# mpc56_clk.net
KiCad netlist of a schematic drawn in Altium Designer
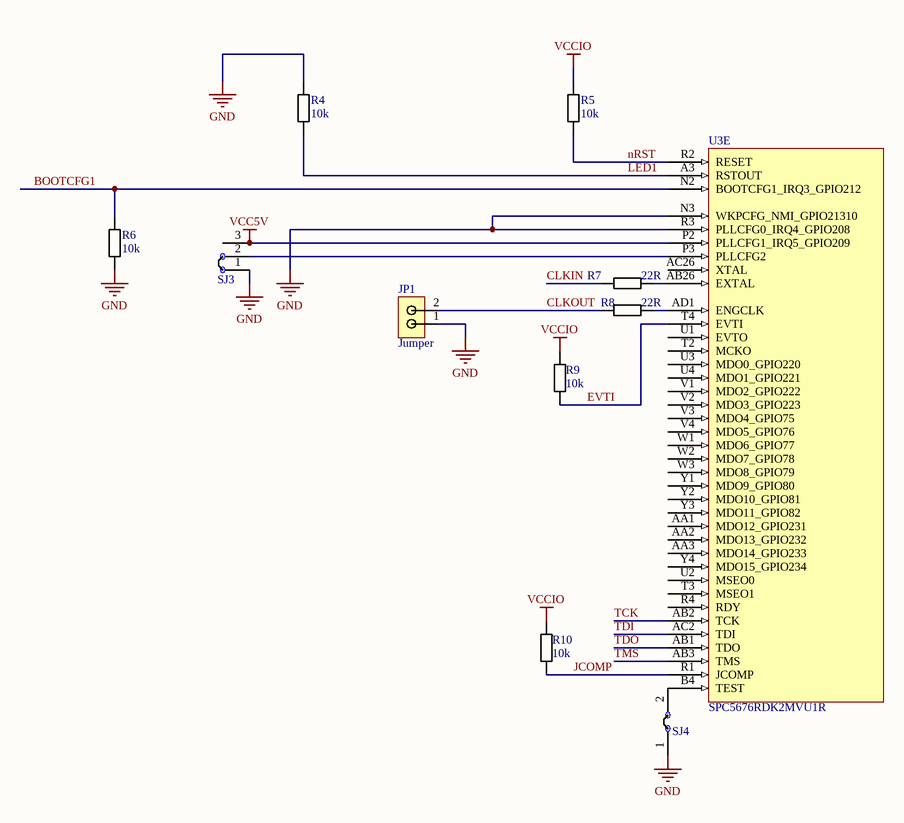
[diagram p0: mpc56_clk.SchDoc]

(export (version "E")
  (design (tool "Eeschema 10.0.6"))
  (components
    (comp (ref "JP1")
      (value "Jumper")
      (footprint "2x2.54mm_Header")
      (description "1x2 2.54mm header, male pins")
      (fields (field (name "PART NUMBER") "2_PIN_JUMPER"))
      (libsource (lib "NewAE_AltiumLib") (part "1x2_Pin_Header"))
    )
    (comp (ref "R4")
      (value "10k")
      (footprint "RESC1608X55N")
      (description "10k res, 0603, 1%, 1/10W")
      (fields (field (name "PART NUMBER") "RCHIP-10K-0603") (field (name "TOLERANCE") "1%"))
      (libsource (lib "NewAE_AltiumLib") (part "RES-EU"))
    )
    (comp (ref "R5")
      (value "10k")
      (footprint "RESC1608X55N")
      (description "10k res, 0603, 1%, 1/10W")
      (fields (field (name "PART NUMBER") "RCHIP-10K-0603") (field (name "TOLERANCE") "1%"))
      (libsource (lib "NewAE_AltiumLib") (part "RES-EU"))
    )
    (comp (ref "R6")
      (value "10k")
      (footprint "RESC1608X55N")
      (description "10k res, 0603, 1%, 1/10W")
      (fields (field (name "PART NUMBER") "RCHIP-10K-0603") (field (name "TOLERANCE") "1%"))
      (libsource (lib "NewAE_AltiumLib") (part "RES-EU"))
    )
    (comp (ref "R7")
      (value "22R")
      (footprint "RESC1608X55N")
      (description "22R res, 0603, 1%, 1/10W")
      (fields (field (name "PART NUMBER") "RCHIP-22R-0603") (field (name "TOLERANCE") "1%"))
      (libsource (lib "") (part "RES-EU_1"))
    )
    (comp (ref "R8")
      (value "22R")
      (footprint "RESC1608X55N")
      (description "22R res, 0603, 1%, 1/10W")
      (fields (field (name "PART NUMBER") "RCHIP-22R-0603") (field (name "TOLERANCE") "1%"))
      (libsource (lib "") (part "RES-EU_1"))
    )
    (comp (ref "R9")
      (value "10k")
      (footprint "RESC1608X55N")
      (description "10k res, 0603, 1%, 1/10W")
      (fields (field (name "PART NUMBER") "RCHIP-10K-0603") (field (name "TOLERANCE") "1%"))
      (libsource (lib "") (part "RES-EU_2"))
    )
    (comp (ref "R10")
      (value "10k")
      (footprint "RESC1608X55N")
      (description "10k res, 0603, 1%, 1/10W")
      (fields (field (name "PART NUMBER") "RCHIP-10K-0603") (field (name "TOLERANCE") "1%"))
      (libsource (lib "NewAE_AltiumLib") (part "RES-EU"))
    )
    (comp (ref "SJ3")
      (value "NC")
      (footprint "SJ_3S_NC12")
      (description "Solder Jumper, NC")
      (fields (field (name "PART NUMBER") "SJ_3S_12JMP"))
      (libsource (lib "NewAE_AltiumLib") (part "SJ_3S_12JMP"))
    )
    (comp (ref "SJ4")
      (value "NC")
      (footprint "SJ_2S_NC")
      (description "Solder Jumper, NC")
      (fields (field (name "PART NUMBER") "SJ_2S"))
      (libsource (lib "NewAE_AltiumLib") (part "SJ_2S"))
    )
    (comp (ref "U3")
      (value "SPC5676RDK2MVU1R")
      (footprint "TEPBGA416_27x27")
      (description "Dual-Core PPC, Automotive")
      (libsource (lib "NewAE_AltiumLib") (part "SPC5676RDK2MVU1R"))
    )
  )
  (nets
    (net (code "1") (name "/BOOTCFG1") (class "Default")
      (node (ref "R6") (pin "1") (pinfunction "1_1") (pintype "passive"))
      (node (ref "U3") (pin "N2") (pinfunction "BOOTCFG1_IRQ3_GPIO212_N2") (pintype "input"))
    )
    (net (code "2") (name "/CLKIN") (class "Default")
      (node (ref "R7") (pin "2") (pinfunction "2_2") (pintype "passive"))
    )
    (net (code "3") (name "/CLKOUT") (class "Default")
      (node (ref "JP1") (pin "2") (pinfunction "2_2") (pintype "passive"))
      (node (ref "R8") (pin "2") (pinfunction "2_2") (pintype "passive"))
    )
    (net (code "4") (name "/EVTI") (class "Default")
      (node (ref "R9") (pin "1") (pinfunction "1_1") (pintype "passive"))
      (node (ref "U3") (pin "T4") (pinfunction "EVTI_T4") (pintype "input"))
    )
    (net (code "5") (name "/JCOMP") (class "Default")
      (node (ref "R10") (pin "2") (pinfunction "2_2") (pintype "passive"))
      (node (ref "U3") (pin "R1") (pinfunction "JCOMP_R1") (pintype "input"))
    )
    (net (code "6") (name "/LED1") (class "Default")
      (node (ref "R4") (pin "2") (pinfunction "2_2") (pintype "passive"))
      (node (ref "U3") (pin "A3") (pinfunction "RSTOUT_A3") (pintype "input"))
    )
    (net (code "7") (name "/TCK") (class "Default")
      (node (ref "U3") (pin "AB2") (pinfunction "TCK_AB2") (pintype "input"))
    )
    (net (code "8") (name "/TDI") (class "Default")
      (node (ref "U3") (pin "AC2") (pinfunction "TDI_AC2") (pintype "input"))
    )
    (net (code "9") (name "/TDO") (class "Default")
      (node (ref "U3") (pin "AB1") (pinfunction "TDO_AB1") (pintype "input"))
    )
    (net (code "10") (name "/TMS") (class "Default")
      (node (ref "U3") (pin "AB3") (pinfunction "TMS_AB3") (pintype "input"))
    )
    (net (code "11") (name "/nRST") (class "Default")
      (node (ref "R5") (pin "2") (pinfunction "2_2") (pintype "passive"))
      (node (ref "U3") (pin "R2") (pinfunction "RESET_R2") (pintype "input"))
    )
    (net (code "12") (name "GND") (class "Default")
      (node (ref "JP1") (pin "1") (pinfunction "1_1") (pintype "passive"))
      (node (ref "R4") (pin "1") (pinfunction "1_1") (pintype "passive"))
      (node (ref "R6") (pin "2") (pinfunction "2_2") (pintype "passive"))
      (node (ref "SJ3") (pin "1") (pinfunction "1_1") (pintype "passive"))
      (node (ref "SJ4") (pin "1") (pinfunction "1_1") (pintype "passive"))
      (node (ref "U3") (pin "N3") (pinfunction "WKPCFG_NMI_GPIO21310_N3") (pintype "input"))
      (node (ref "U3") (pin "R3") (pinfunction "PLLCFG0_IRQ4_GPIO208_R3") (pintype "input"))
    )
    (net (code "13") (name "Net-(U3E-ENGCLK)") (class "Default")
      (node (ref "R8") (pin "1") (pinfunction "1_1") (pintype "passive"))
      (node (ref "U3") (pin "AD1") (pinfunction "ENGCLK_AD1") (pintype "input"))
    )
    (net (code "14") (name "Net-(U3E-EXTAL)") (class "Default")
      (node (ref "R7") (pin "1") (pinfunction "1_1") (pintype "passive"))
      (node (ref "U3") (pin "AB26") (pinfunction "EXTAL_AB26") (pintype "input"))
    )
    (net (code "15") (name "Net-(U3E-PLLCFG2)") (class "Default")
      (node (ref "SJ3") (pin "2") (pinfunction "2_2") (pintype "passive"))
      (node (ref "U3") (pin "P3") (pinfunction "PLLCFG2_P3") (pintype "input"))
    )
    (net (code "16") (name "Net-(U3E-TEST)") (class "Default")
      (node (ref "SJ4") (pin "2") (pinfunction "2_2") (pintype "passive"))
      (node (ref "U3") (pin "B4") (pinfunction "TEST_B4") (pintype "input"))
    )
    (net (code "17") (name "VCC5V") (class "Default")
      (node (ref "SJ3") (pin "3") (pinfunction "3_3") (pintype "passive"))
      (node (ref "U3") (pin "P2") (pinfunction "PLLCFG1_IRQ5_GPIO209_P2") (pintype "input"))
    )
    (net (code "18") (name "VCCIO") (class "Default")
      (node (ref "R10") (pin "1") (pinfunction "1_1") (pintype "passive"))
      (node (ref "R5") (pin "1") (pinfunction "1_1") (pintype "passive"))
      (node (ref "R9") (pin "2") (pinfunction "2_2") (pintype "passive"))
    )
    (net (code "19") (name "unconnected-(U3E-EVTO-PadU1)") (class "Default")
      (node (ref "U3") (pin "U1") (pinfunction "EVTO_U1") (pintype "input"))
    )
    (net (code "20") (name "unconnected-(U3E-MCKO-PadT2)") (class "Default")
      (node (ref "U3") (pin "T2") (pinfunction "MCKO_T2") (pintype "input"))
    )
    (net (code "21") (name "unconnected-(U3E-MDO0_GPIO220-PadU3)") (class "Default")
      (node (ref "U3") (pin "U3") (pinfunction "MDO0_GPIO220_U3") (pintype "input"))
    )
    (net (code "22") (name "unconnected-(U3E-MDO1_GPIO221-PadU4)") (class "Default")
      (node (ref "U3") (pin "U4") (pinfunction "MDO1_GPIO221_U4") (pintype "input"))
    )
    (net (code "23") (name "unconnected-(U3E-MDO2_GPIO222-PadV1)") (class "Default")
      (node (ref "U3") (pin "V1") (pinfunction "MDO2_GPIO222_V1") (pintype "input"))
    )
    (net (code "24") (name "unconnected-(U3E-MDO3_GPIO223-PadV2)") (class "Default")
      (node (ref "U3") (pin "V2") (pinfunction "MDO3_GPIO223_V2") (pintype "input"))
    )
    (net (code "25") (name "unconnected-(U3E-MDO4_GPIO75-PadV3)") (class "Default")
      (node (ref "U3") (pin "V3") (pinfunction "MDO4_GPIO75_V3") (pintype "input"))
    )
    (net (code "26") (name "unconnected-(U3E-MDO5_GPIO76-PadV4)") (class "Default")
      (node (ref "U3") (pin "V4") (pinfunction "MDO5_GPIO76_V4") (pintype "input"))
    )
    (net (code "27") (name "unconnected-(U3E-MDO6_GPIO77-PadW1)") (class "Default")
      (node (ref "U3") (pin "W1") (pinfunction "MDO6_GPIO77_W1") (pintype "input"))
    )
    (net (code "28") (name "unconnected-(U3E-MDO7_GPIO78-PadW2)") (class "Default")
      (node (ref "U3") (pin "W2") (pinfunction "MDO7_GPIO78_W2") (pintype "input"))
    )
    (net (code "29") (name "unconnected-(U3E-MDO8_GPIO79-PadW3)") (class "Default")
      (node (ref "U3") (pin "W3") (pinfunction "MDO8_GPIO79_W3") (pintype "input"))
    )
    (net (code "30") (name "unconnected-(U3E-MDO9_GPIO80-PadY1)") (class "Default")
      (node (ref "U3") (pin "Y1") (pinfunction "MDO9_GPIO80_Y1") (pintype "input"))
    )
    (net (code "31") (name "unconnected-(U3E-MDO10_GPIO81-PadY2)") (class "Default")
      (node (ref "U3") (pin "Y2") (pinfunction "MDO10_GPIO81_Y2") (pintype "input"))
    )
    (net (code "32") (name "unconnected-(U3E-MDO11_GPIO82-PadY3)") (class "Default")
      (node (ref "U3") (pin "Y3") (pinfunction "MDO11_GPIO82_Y3") (pintype "input"))
    )
    (net (code "33") (name "unconnected-(U3E-MDO12_GPIO231-PadAA1)") (class "Default")
      (node (ref "U3") (pin "AA1") (pinfunction "MDO12_GPIO231_AA1") (pintype "input"))
    )
    (net (code "34") (name "unconnected-(U3E-MDO13_GPIO232-PadAA2)") (class "Default")
      (node (ref "U3") (pin "AA2") (pinfunction "MDO13_GPIO232_AA2") (pintype "input"))
    )
    (net (code "35") (name "unconnected-(U3E-MDO14_GPIO233-PadAA3)") (class "Default")
      (node (ref "U3") (pin "AA3") (pinfunction "MDO14_GPIO233_AA3") (pintype "input"))
    )
    (net (code "36") (name "unconnected-(U3E-MDO15_GPIO234-PadY4)") (class "Default")
      (node (ref "U3") (pin "Y4") (pinfunction "MDO15_GPIO234_Y4") (pintype "input"))
    )
    (net (code "37") (name "unconnected-(U3E-MSEO0-PadU2)") (class "Default")
      (node (ref "U3") (pin "U2") (pinfunction "MSEO0_U2") (pintype "input"))
    )
    (net (code "38") (name "unconnected-(U3E-MSEO1-PadT3)") (class "Default")
      (node (ref "U3") (pin "T3") (pinfunction "MSEO1_T3") (pintype "input"))
    )
    (net (code "39") (name "unconnected-(U3E-RDY-PadR4)") (class "Default")
      (node (ref "U3") (pin "R4") (pinfunction "RDY_R4") (pintype "input"))
    )
    (net (code "40") (name "unconnected-(U3E-XTAL-PadAC26)") (class "Default")
      (node (ref "U3") (pin "AC26") (pinfunction "XTAL_AC26") (pintype "input"))
    )
  )
)
